# EDP_and_MIPI_DSI_Connectors.net
KiCad netlist of a schematic drawn in Altium Designer
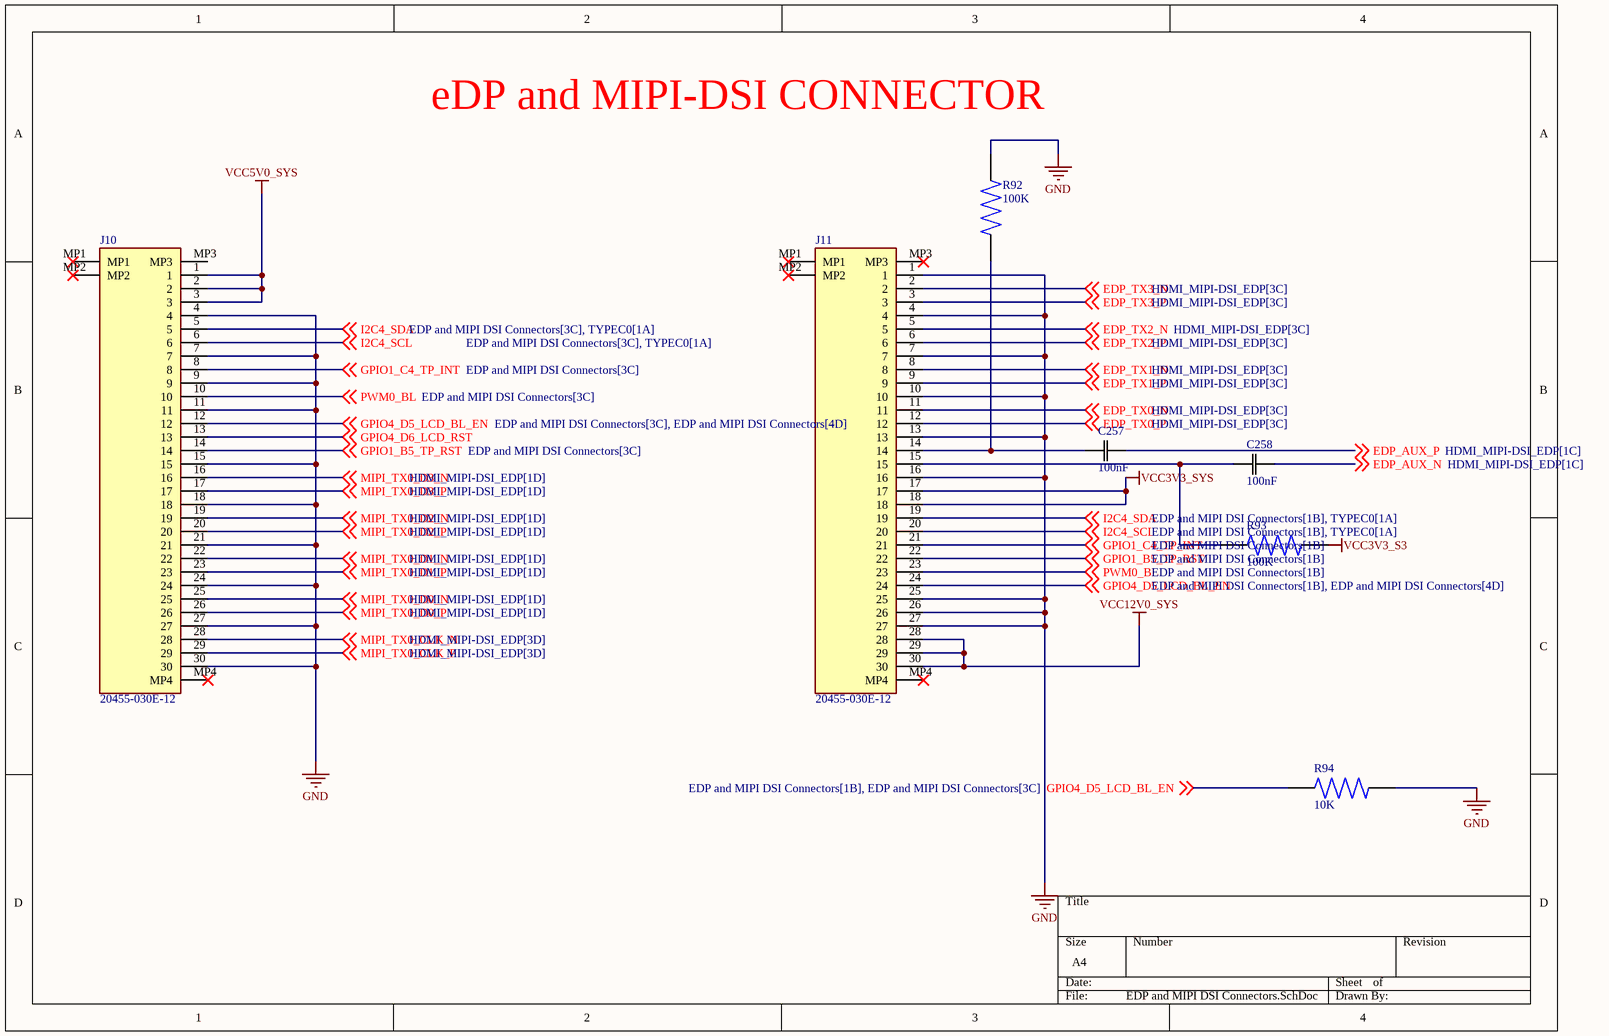
[diagram p0: EDP and MIPI DSI Connectors.SchDoc]

(export (version "E")
  (design (tool "Eeschema 10.0.6"))
  (components
    (comp (ref "C257")
      (value "100nF")
      (footprint "CAP_1005_TDK")
      (description "Description")
      (fields
        (field (name "MANUFACTURER_PART_NUMBER") "C1005X7R1H104M050BB")
        (field (name "COPYRIGHT") "Copyright (C) 2025 Ultra Librarian. All rights reserved.")
      )
      (libsource (lib "C1005X7R1H104M050BB") (part "C1005X7R1H104M050BB"))
    )
    (comp (ref "C258")
      (value "100nF")
      (footprint "CAP_1005_TDK")
      (description "Description")
      (fields
        (field (name "MANUFACTURER_PART_NUMBER") "C1005X7R1H104M050BB")
        (field (name "COPYRIGHT") "Copyright (C) 2025 Ultra Librarian. All rights reserved.")
      )
      (libsource (lib "C1005X7R1H104M050BB") (part "C1005X7R1H104M050BB"))
    )
    (comp (ref "J10")
      (value "20455-030E-12")
      (footprint "20455030E12")
      (description "Board Connector, 30 Contact(s), 1 Row(s), Female, Right Angle, Surface Mount Terminal, Receptacle")
      (libsource (lib "20455-030E-12") (part "20455-030E-12"))
    )
    (comp (ref "J11")
      (value "20455-030E-12")
      (footprint "20455030E12")
      (description "Board Connector, 30 Contact(s), 1 Row(s), Female, Right Angle, Surface Mount Terminal, Receptacle")
      (libsource (lib "20455-030E-12") (part "20455-030E-12"))
    )
    (comp (ref "R92")
      (value "100K")
      (footprint "RES_ERA3ARB103V")
      (fields (field (name "MP") "ERA3ARB103V"))
      (libsource (lib "ERA3ARB103V") (part "ERA3ARB103V"))
    )
    (comp (ref "R93")
      (value "100K")
      (footprint "RES_ERA3ARB103V")
      (fields (field (name "MP") "ERA3ARB103V"))
      (libsource (lib "ERA3ARB103V") (part "ERA3ARB103V"))
    )
    (comp (ref "R94")
      (value "10K")
      (footprint "RES_ERA3ARB103V")
      (fields (field (name "MP") "ERA3ARB103V"))
      (libsource (lib "ERA3ARB103V") (part "ERA3ARB103V"))
    )
  )
  (nets
    (net (code "1") (name "EDP_AUX_N") (class "Default")
      (node (ref "C258") (pin "1") (pinfunction "1_1") (pintype "passive"))
    )
    (net (code "2") (name "EDP_AUX_P") (class "Default")
      (node (ref "C257") (pin "1") (pinfunction "1_1") (pintype "passive"))
    )
    (net (code "3") (name "EDP_TX0_N") (class "Default")
      (node (ref "J11") (pin "11") (pinfunction "11_11") (pintype "passive"))
    )
    (net (code "4") (name "EDP_TX0_P") (class "Default")
      (node (ref "J11") (pin "12") (pinfunction "12_12") (pintype "passive"))
    )
    (net (code "5") (name "EDP_TX1_N") (class "Default")
      (node (ref "J11") (pin "8") (pinfunction "8_8") (pintype "passive"))
    )
    (net (code "6") (name "EDP_TX1_P") (class "Default")
      (node (ref "J11") (pin "9") (pinfunction "9_9") (pintype "passive"))
    )
    (net (code "7") (name "EDP_TX2_N") (class "Default")
      (node (ref "J11") (pin "5") (pinfunction "5_5") (pintype "passive"))
    )
    (net (code "8") (name "EDP_TX2_P") (class "Default")
      (node (ref "J11") (pin "6") (pinfunction "6_6") (pintype "passive"))
    )
    (net (code "9") (name "EDP_TX3_N") (class "Default")
      (node (ref "J11") (pin "2") (pinfunction "2_2") (pintype "passive"))
    )
    (net (code "10") (name "EDP_TX3_P") (class "Default")
      (node (ref "J11") (pin "3") (pinfunction "3_3") (pintype "passive"))
    )
    (net (code "11") (name "GND") (class "Default")
      (node (ref "J10") (pin "11") (pinfunction "11_11") (pintype "passive"))
      (node (ref "J10") (pin "15") (pinfunction "15_15") (pintype "passive"))
      (node (ref "J10") (pin "18") (pinfunction "18_18") (pintype "passive"))
      (node (ref "J10") (pin "21") (pinfunction "21_21") (pintype "passive"))
      (node (ref "J10") (pin "24") (pinfunction "24_24") (pintype "passive"))
      (node (ref "J10") (pin "27") (pinfunction "27_27") (pintype "passive"))
      (node (ref "J10") (pin "30") (pinfunction "30_30") (pintype "passive"))
      (node (ref "J10") (pin "4") (pinfunction "4_4") (pintype "passive"))
      (node (ref "J10") (pin "7") (pinfunction "7_7") (pintype "passive"))
      (node (ref "J10") (pin "9") (pinfunction "9_9") (pintype "passive"))
      (node (ref "J11") (pin "1") (pinfunction "1_1") (pintype "passive"))
      (node (ref "J11") (pin "10") (pinfunction "10_10") (pintype "passive"))
      (node (ref "J11") (pin "13") (pinfunction "13_13") (pintype "passive"))
      (node (ref "J11") (pin "16") (pinfunction "16_16") (pintype "passive"))
      (node (ref "J11") (pin "25") (pinfunction "25_25") (pintype "passive"))
      (node (ref "J11") (pin "26") (pinfunction "26_26") (pintype "passive"))
      (node (ref "J11") (pin "27") (pinfunction "27_27") (pintype "passive"))
      (node (ref "J11") (pin "4") (pinfunction "4_4") (pintype "passive"))
      (node (ref "J11") (pin "7") (pinfunction "7_7") (pintype "passive"))
      (node (ref "R92") (pin "2") (pinfunction "2_2") (pintype "passive"))
      (node (ref "R94") (pin "1") (pinfunction "1_1") (pintype "passive"))
    )
    (net (code "12") (name "GPIO1_B5_TP_RST") (class "Default")
      (node (ref "J10") (pin "14") (pinfunction "14_14") (pintype "passive"))
      (node (ref "J11") (pin "22") (pinfunction "22_22") (pintype "passive"))
    )
    (net (code "13") (name "GPIO1_C4_TP_INT") (class "Default")
      (node (ref "J10") (pin "8") (pinfunction "8_8") (pintype "passive"))
      (node (ref "J11") (pin "21") (pinfunction "21_21") (pintype "passive"))
    )
    (net (code "14") (name "GPIO4_D5_LCD_BL_EN") (class "Default")
      (node (ref "J10") (pin "12") (pinfunction "12_12") (pintype "passive"))
      (node (ref "J11") (pin "24") (pinfunction "24_24") (pintype "passive"))
      (node (ref "R94") (pin "2") (pinfunction "2_2") (pintype "passive"))
    )
    (net (code "15") (name "GPIO4_D6_LCD_RST") (class "Default")
      (node (ref "J10") (pin "13") (pinfunction "13_13") (pintype "passive"))
    )
    (net (code "16") (name "I2C4_SCL") (class "Default")
      (node (ref "J10") (pin "6") (pinfunction "6_6") (pintype "passive"))
      (node (ref "J11") (pin "20") (pinfunction "20_20") (pintype "passive"))
    )
    (net (code "17") (name "I2C4_SDA") (class "Default")
      (node (ref "J10") (pin "5") (pinfunction "5_5") (pintype "passive"))
      (node (ref "J11") (pin "19") (pinfunction "19_19") (pintype "passive"))
    )
    (net (code "18") (name "MIPI_TX0_CLK_N") (class "Default")
      (node (ref "J10") (pin "28") (pinfunction "28_28") (pintype "passive"))
    )
    (net (code "19") (name "MIPI_TX0_CLK_P") (class "Default")
      (node (ref "J10") (pin "29") (pinfunction "29_29") (pintype "passive"))
    )
    (net (code "20") (name "MIPI_TX0_D0_N") (class "Default")
      (node (ref "J10") (pin "25") (pinfunction "25_25") (pintype "passive"))
    )
    (net (code "21") (name "MIPI_TX0_D0_P") (class "Default")
      (node (ref "J10") (pin "26") (pinfunction "26_26") (pintype "passive"))
    )
    (net (code "22") (name "MIPI_TX0_D1_N") (class "Default")
      (node (ref "J10") (pin "22") (pinfunction "22_22") (pintype "passive"))
    )
    (net (code "23") (name "MIPI_TX0_D1_P") (class "Default")
      (node (ref "J10") (pin "23") (pinfunction "23_23") (pintype "passive"))
    )
    (net (code "24") (name "MIPI_TX0_D2_N") (class "Default")
      (node (ref "J10") (pin "19") (pinfunction "19_19") (pintype "passive"))
    )
    (net (code "25") (name "MIPI_TX0_D2_P") (class "Default")
      (node (ref "J10") (pin "20") (pinfunction "20_20") (pintype "passive"))
    )
    (net (code "26") (name "MIPI_TX0_D3_N") (class "Default")
      (node (ref "J10") (pin "16") (pinfunction "16_16") (pintype "passive"))
    )
    (net (code "27") (name "MIPI_TX0_D3_P") (class "Default")
      (node (ref "J10") (pin "17") (pinfunction "17_17") (pintype "passive"))
    )
    (net (code "28") (name "Net-(C257-Pad2)") (class "Default")
      (node (ref "C257") (pin "2") (pinfunction "2_2") (pintype "passive"))
      (node (ref "J11") (pin "14") (pinfunction "14_14") (pintype "passive"))
      (node (ref "R92") (pin "1") (pinfunction "1_1") (pintype "passive"))
    )
    (net (code "29") (name "Net-(C258-Pad2)") (class "Default")
      (node (ref "C258") (pin "2") (pinfunction "2_2") (pintype "passive"))
      (node (ref "J11") (pin "15") (pinfunction "15_15") (pintype "passive"))
      (node (ref "R93") (pin "2") (pinfunction "2_2") (pintype "passive"))
    )
    (net (code "30") (name "PWM0_BL") (class "Default")
      (node (ref "J10") (pin "10") (pinfunction "10_10") (pintype "passive"))
      (node (ref "J11") (pin "23") (pinfunction "23_23") (pintype "passive"))
    )
    (net (code "31") (name "VCC3V3_S3") (class "Default")
      (node (ref "R93") (pin "1") (pinfunction "1_1") (pintype "passive"))
    )
    (net (code "32") (name "VCC3V3_SYS") (class "Default")
      (node (ref "J11") (pin "17") (pinfunction "17_17") (pintype "passive"))
      (node (ref "J11") (pin "18") (pinfunction "18_18") (pintype "passive"))
    )
    (net (code "33") (name "VCC5V0_SYS") (class "Default")
      (node (ref "J10") (pin "1") (pinfunction "1_1") (pintype "passive"))
      (node (ref "J10") (pin "2") (pinfunction "2_2") (pintype "passive"))
      (node (ref "J10") (pin "3") (pinfunction "3_3") (pintype "passive"))
    )
    (net (code "34") (name "VCC12V0_SYS") (class "Default")
      (node (ref "J11") (pin "28") (pinfunction "28_28") (pintype "passive"))
      (node (ref "J11") (pin "29") (pinfunction "29_29") (pintype "passive"))
      (node (ref "J11") (pin "30") (pinfunction "30_30") (pintype "passive"))
    )
    (net (code "35") (name "unconnected-(J10-PadMP1)") (class "Default")
      (node (ref "J10") (pin "MP1") (pinfunction "MP1_MP1") (pintype "passive+no_connect"))
    )
    (net (code "36") (name "unconnected-(J10-PadMP2)") (class "Default")
      (node (ref "J10") (pin "MP2") (pinfunction "MP2_MP2") (pintype "passive+no_connect"))
    )
    (net (code "37") (name "unconnected-(J10-PadMP3)") (class "Default")
      (node (ref "J10") (pin "MP3") (pinfunction "MP3_MP3") (pintype "passive"))
    )
    (net (code "38") (name "unconnected-(J10-PadMP4)") (class "Default")
      (node (ref "J10") (pin "MP4") (pinfunction "MP4_MP4") (pintype "passive+no_connect"))
    )
    (net (code "39") (name "unconnected-(J11-PadMP1)") (class "Default")
      (node (ref "J11") (pin "MP1") (pinfunction "MP1_MP1") (pintype "passive+no_connect"))
    )
    (net (code "40") (name "unconnected-(J11-PadMP2)") (class "Default")
      (node (ref "J11") (pin "MP2") (pinfunction "MP2_MP2") (pintype "passive+no_connect"))
    )
    (net (code "41") (name "unconnected-(J11-PadMP3)") (class "Default")
      (node (ref "J11") (pin "MP3") (pinfunction "MP3_MP3") (pintype "passive+no_connect"))
    )
    (net (code "42") (name "unconnected-(J11-PadMP4)") (class "Default")
      (node (ref "J11") (pin "MP4") (pinfunction "MP4_MP4") (pintype "passive+no_connect"))
    )
  )
)
